# Aux_Outputs.net
KiCad netlist of a schematic drawn in Altium Designer
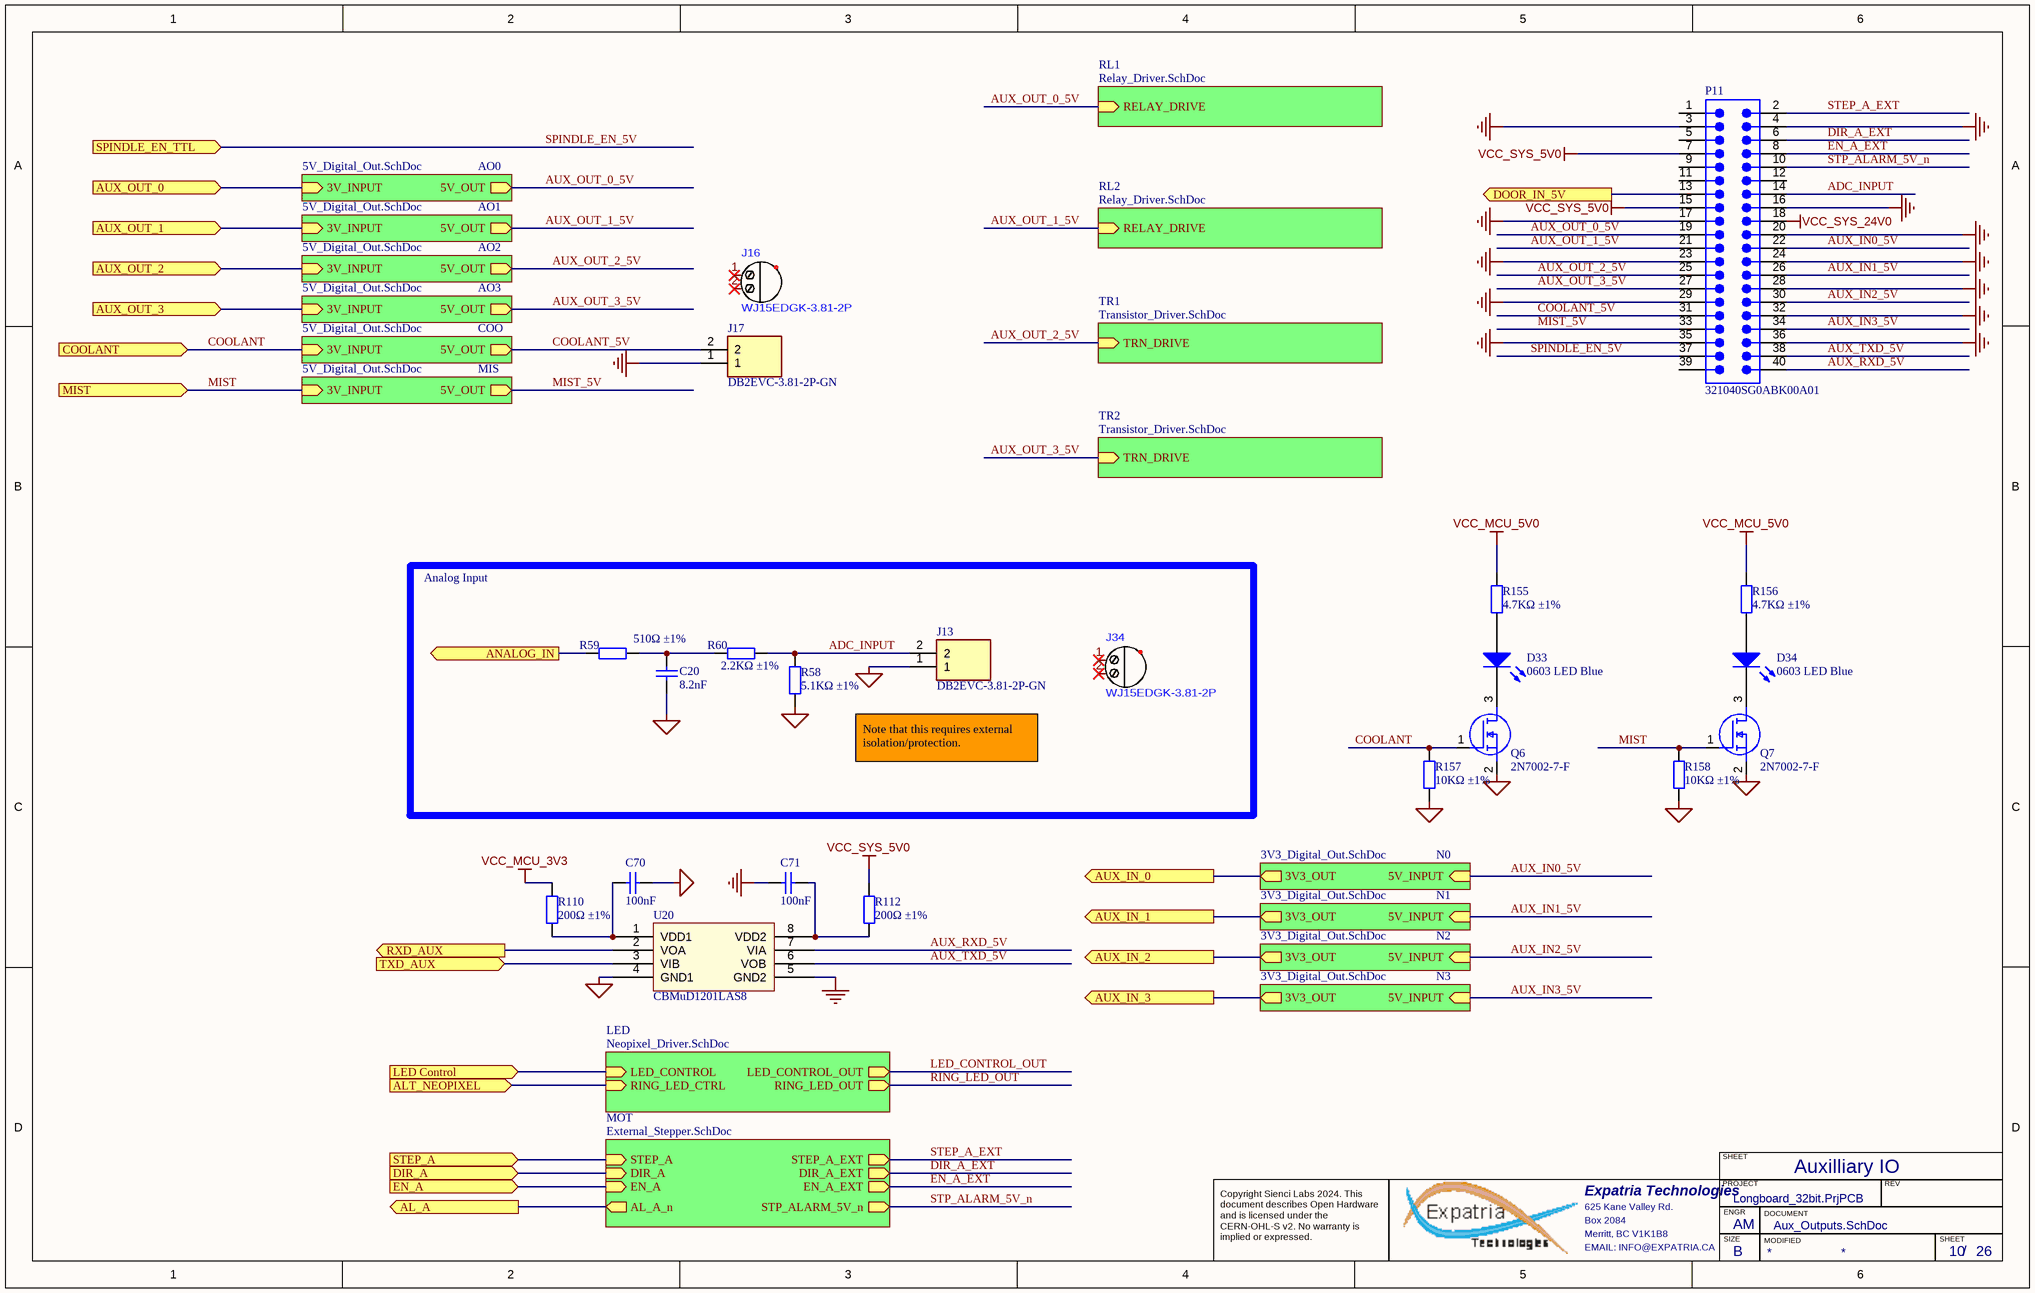
[diagram p0: Aux_Outputs.SchDoc]

(export (version "E")
  (design (tool "Eeschema 10.0.6"))
  (components
    (comp (ref "C20")
      (value "8.2nF")
      (footprint "0603_C")
      (description "50V 8.2nF X7R ±10% 0603 Multilayer Ceramic Capacitors MLCC - SMD/SMT ROHS")
      (fields (field (name "MANUFACTURER") "YAGEO") (field (name "TOLERANCE") "10%"))
      (libsource (lib "Sienci_Labs") (part "0603 8.2nF (822) 10% 50V"))
    )
    (comp (ref "C70")
      (value "100nF")
      (footprint "0402_C")
      (description "16V 100nF X7R ±10% 0402 Multilayer Ceramic Capacitors MLCC - SMD/SMT ROHS")
      (fields (field (name "MANUFACTURER") "Samsung Electro-Mechanics") (field (name "TOLERANCE") "10%"))
      (libsource (lib "Sienci_Labs") (part "0402 100nF (104) 10% 16V"))
    )
    (comp (ref "C71")
      (value "100nF")
      (footprint "0402_C")
      (description "16V 100nF X7R ±10% 0402 Multilayer Ceramic Capacitors MLCC - SMD/SMT ROHS")
      (fields (field (name "MANUFACTURER") "Samsung Electro-Mechanics") (field (name "TOLERANCE") "10%"))
      (libsource (lib "Sienci_Labs") (part "0402 100nF (104) 10% 16V"))
    )
    (comp (ref "D33")
      (value "0603 LED Blue")
      (footprint "0603_LED_S1 - BLUE")
      (description "Colorless transparence -40℃~+85℃ 465nm~475nm blue 120° 110mW 0603 Light Emitting Diodes (LED) ROHS")
      (fields
        (field (name "MANUFACTURER") "Everlight Elec")
        (field (name "MANUFACTURER PART NUMBER") "19-217/BHC-ZL1M2RY/3T")
      )
      (libsource (lib "Sienci_Labs") (part "0603 LED Blue"))
    )
    (comp (ref "D34")
      (value "0603 LED Blue")
      (footprint "0603_LED_S1 - BLUE")
      (description "Colorless transparence -40℃~+85℃ 465nm~475nm blue 120° 110mW 0603 Light Emitting Diodes (LED) ROHS")
      (fields
        (field (name "MANUFACTURER") "Everlight Elec")
        (field (name "MANUFACTURER PART NUMBER") "19-217/BHC-ZL1M2RY/3T")
      )
      (libsource (lib "Sienci_Labs") (part "0603 LED Blue"))
    )
    (comp (ref "J13")
      (value "DB2EVC-3.81-2P-GN")
      (footprint "CONN-TH_5P-P3.81_DB2EVC-3.81-2p")
      (description "3.81mm Green Board Edge/Receptacle-Close Push-Pull,P=3.81mm Pluggable System Terminal Block ROHS")
      (fields (field (name "MANUFACTURER") "DIBO"))
      (libsource (lib "Sienci_Labs") (part "DB2EVC-3.81-2P-GN"))
    )
    (comp (ref "J16")
      (value "WJ15EDGK-3.81-2P")
      (description "2 1 3.81mm Green Plug P=3.81mm Pluggable System Terminal Block ROHS")
      (fields (field (name "MANUFACTURER") "Ningbo"))
      (libsource (lib "Sienci_Labs") (part "WJ15EDGK-3.81-2P"))
    )
    (comp (ref "J17")
      (value "DB2EVC-3.81-2P-GN")
      (footprint "CONN-TH_5P-P3.81_DB2EVC-3.81-2p")
      (description "3.81mm Green Board Edge/Receptacle-Close Push-Pull,P=3.81mm Pluggable System Terminal Block ROHS")
      (fields (field (name "MANUFACTURER") "DIBO"))
      (libsource (lib "Sienci_Labs") (part "DB2EVC-3.81-2P-GN"))
    )
    (comp (ref "J34")
      (value "WJ15EDGK-3.81-2P")
      (description "2 1 3.81mm Green Plug P=3.81mm Pluggable System Terminal Block ROHS")
      (fields (field (name "MANUFACTURER") "Ningbo"))
      (libsource (lib "Sienci_Labs") (part "WJ15EDGK-3.81-2P"))
    )
    (comp (ref "P11")
      (value "321040SG0ABK00A01")
      (footprint "IDC-TH_40P-P2.54_321040SG0ABK00A01")
      (description "2.54mm Straight Gold Brass 20 Push - Pull 2.54mm 2 Straight,P=2.54mm IDC Connectors ROHS")
      (fields (field (name "MANUFACTURER") "JILN"))
      (libsource (lib "Sienci_Labs") (part "321040SG0ABK00A01"))
    )
    (comp (ref "Q6")
      (value "2N7002-7-F")
      (footprint "SOT-23(SOT-23-3)")
      (description "60V 115mA 7.5Ω@5V,50mA 370mW N Channel SOT-23 MOSFETs ROHS")
      (fields (field (name "MANUFACTURER") "Diodes Inc.") (field (name "MOUSER PART NUMBER") "621-2N7002-F"))
      (libsource (lib "Sienci_Labs") (part "2N7002-7-F"))
    )
    (comp (ref "Q7")
      (value "2N7002-7-F")
      (footprint "SOT-23(SOT-23-3)")
      (description "60V 115mA 7.5Ω@5V,50mA 370mW N Channel SOT-23 MOSFETs ROHS")
      (fields (field (name "MANUFACTURER") "Diodes Inc.") (field (name "MOUSER PART NUMBER") "621-2N7002-F"))
      (libsource (lib "Sienci_Labs") (part "2N7002-7-F"))
    )
    (comp (ref "R58")
      (value "5.1KΩ ±1%")
      (footprint "0402_R")
      (description "Chip resistor")
      (fields
        (field (name "MANUFACTURER") "Uniroyal Elec")
        (field (name "MANUFACTURER PART NUMBER") "0402WGF5101TCE")
      )
      (libsource (lib "RES") (part "0402 5.1K (5101) 1%"))
    )
    (comp (ref "R59")
      (value "510Ω ±1%")
      (footprint "0402_R")
      (description "Chip resistor")
      (fields
        (field (name "MANUFACTURER") "Uniroyal Elec")
        (field (name "MANUFACTURER PART NUMBER") "0402WGF5100TCE")
      )
      (libsource (lib "Sienci_Labs") (part "0402 510R (5100) 1%"))
    )
    (comp (ref "R60")
      (value "2.2KΩ ±1%")
      (footprint "0402_R")
      (description "Chip resistor")
      (fields
        (field (name "MANUFACTURER") "Uniroyal Elec")
        (field (name "MANUFACTURER PART NUMBER") "0402WGF2201TCE")
      )
      (libsource (lib "RES") (part "0402 2.2K (2201) 1%"))
    )
    (comp (ref "R110")
      (value "200Ω ±1%")
      (footprint "0402_R")
      (description "Chip resistor")
      (fields
        (field (name "MANUFACTURER") "Uniroyal Elec")
        (field (name "MANUFACTURER PART NUMBER") "0402WGF2000TCE")
      )
      (libsource (lib "RES") (part "0402 200R (2000) 1%"))
    )
    (comp (ref "R112")
      (value "200Ω ±1%")
      (footprint "0402_R")
      (description "Chip resistor")
      (fields
        (field (name "MANUFACTURER") "Uniroyal Elec")
        (field (name "MANUFACTURER PART NUMBER") "0402WGF2000TCE")
      )
      (libsource (lib "RES") (part "0402 200R (2000) 1%"))
    )
    (comp (ref "R155")
      (value "4.7KΩ ±1%")
      (footprint "0402_R")
      (description "Chip resistor")
      (fields
        (field (name "MANUFACTURER") "Uniroyal Elec")
        (field (name "MANUFACTURER PART NUMBER") "0402WGF4701TCE")
      )
      (libsource (lib "RES") (part "0402 4.7K (4701) 1%"))
    )
    (comp (ref "R156")
      (value "4.7KΩ ±1%")
      (footprint "0402_R")
      (description "Chip resistor")
      (fields
        (field (name "MANUFACTURER") "Uniroyal Elec")
        (field (name "MANUFACTURER PART NUMBER") "0402WGF4701TCE")
      )
      (libsource (lib "RES") (part "0402 4.7K (4701) 1%"))
    )
    (comp (ref "R157")
      (value "10KΩ ±1%")
      (footprint "0603_R")
      (description "Chip resistor")
      (fields
        (field (name "MANUFACTURER") "Uniroyal Elec")
        (field (name "MANUFACTURER PART NUMBER") "0603WAF1002T5E")
      )
      (libsource (lib "RES") (part "0603 10K (1002) 1%"))
    )
    (comp (ref "R158")
      (value "10KΩ ±1%")
      (footprint "0603_R")
      (description "Chip resistor")
      (fields
        (field (name "MANUFACTURER") "Uniroyal Elec")
        (field (name "MANUFACTURER PART NUMBER") "0603WAF1002T5E")
      )
      (libsource (lib "RES") (part "0603 10K (1002) 1%"))
    )
    (comp (ref "U20")
      (value "CBMuD1201LAS8")
      (footprint "SOIC-8_150mil")
      (description "Dual Channel Isolator")
      (fields (field (name "MANUFACTURER") "Corebai Microelectronics"))
      (libsource (lib "Sienci_Labs") (part "CBMuD1201LAS8"))
    )
  )
  (nets
    (net (code "1") (name "/ADC_INPUT") (class "Default")
      (node (ref "J13") (pin "2") (pinfunction "2_2") (pintype "passive"))
      (node (ref "P11") (pin "14") (pinfunction "14_14") (pintype "passive"))
      (node (ref "R58") (pin "2") (pinfunction "2_2") (pintype "passive"))
      (node (ref "R60") (pin "2") (pinfunction "2_2") (pintype "passive"))
    )
    (net (code "4") (name "/ANALOG_IN") (class "Default")
      (node (ref "R59") (pin "1") (pinfunction "1_1") (pintype "passive"))
    )
    (net (code "5") (name "/AUX_IN0_5V") (class "Default")
      (node (ref "P11") (pin "22") (pinfunction "22_22") (pintype "passive"))
    )
    (net (code "6") (name "/AUX_IN1_5V") (class "Default")
      (node (ref "P11") (pin "26") (pinfunction "26_26") (pintype "passive"))
    )
    (net (code "7") (name "/AUX_IN2_5V") (class "Default")
      (node (ref "P11") (pin "30") (pinfunction "30_30") (pintype "passive"))
    )
    (net (code "8") (name "/AUX_IN3_5V") (class "Default")
      (node (ref "P11") (pin "34") (pinfunction "34_34") (pintype "passive"))
    )
    (net (code "14") (name "/AUX_OUT_0_5V") (class "Default")
      (node (ref "P11") (pin "19") (pinfunction "19_19") (pintype "passive"))
    )
    (net (code "16") (name "/AUX_OUT_1_5V") (class "Default")
      (node (ref "P11") (pin "21") (pinfunction "21_21") (pintype "passive"))
    )
    (net (code "18") (name "/AUX_OUT_2_5V") (class "Default")
      (node (ref "P11") (pin "25") (pinfunction "25_25") (pintype "passive"))
    )
    (net (code "20") (name "/AUX_OUT_3_5V") (class "Default")
      (node (ref "P11") (pin "27") (pinfunction "27_27") (pintype "passive"))
    )
    (net (code "21") (name "/AUX_RXD_5V") (class "Default")
      (node (ref "P11") (pin "40") (pinfunction "40_40") (pintype "passive"))
      (node (ref "U20") (pin "7") (pinfunction "VIA_7") (pintype "passive"))
    )
    (net (code "22") (name "/AUX_TXD_5V") (class "Default")
      (node (ref "P11") (pin "38") (pinfunction "38_38") (pintype "passive"))
      (node (ref "U20") (pin "6") (pinfunction "VOB_6") (pintype "passive"))
    )
    (net (code "23") (name "/COOLANT") (class "Default")
      (node (ref "Q6") (pin "1") (pinfunction "G_1") (pintype "passive"))
      (node (ref "R157") (pin "2") (pinfunction "2_2") (pintype "passive"))
    )
    (net (code "24") (name "/COOLANT_5V") (class "Default")
      (node (ref "J17") (pin "2") (pinfunction "2_2") (pintype "passive"))
      (node (ref "P11") (pin "31") (pinfunction "31_31") (pintype "passive"))
    )
    (net (code "26") (name "/DIR_A_EXT") (class "Default")
      (node (ref "P11") (pin "6") (pinfunction "6_6") (pintype "passive"))
    )
    (net (code "27") (name "/DOOR_IN_5V") (class "Default")
      (node (ref "P11") (pin "13") (pinfunction "13_13") (pintype "passive"))
    )
    (net (code "29") (name "/EN_A_EXT") (class "Default")
      (node (ref "P11") (pin "8") (pinfunction "8_8") (pintype "passive"))
    )
    (net (code "32") (name "/MIST") (class "Default")
      (node (ref "Q7") (pin "1") (pinfunction "G_1") (pintype "passive"))
      (node (ref "R158") (pin "2") (pinfunction "2_2") (pintype "passive"))
    )
    (net (code "33") (name "/MIST_5V") (class "Default")
      (node (ref "P11") (pin "33") (pinfunction "33_33") (pintype "passive"))
    )
    (net (code "35") (name "/RXD_AUX") (class "Default")
      (node (ref "U20") (pin "2") (pinfunction "VOA_2") (pintype "passive"))
    )
    (net (code "36") (name "/SPINDLE_EN_5V") (class "Default")
      (node (ref "P11") (pin "37") (pinfunction "37_37") (pintype "passive"))
    )
    (net (code "38") (name "/STEP_A_EXT") (class "Default")
      (node (ref "P11") (pin "2") (pinfunction "2_2") (pintype "passive"))
    )
    (net (code "39") (name "/STP_ALARM_5V_n") (class "Default")
      (node (ref "P11") (pin "10") (pinfunction "10_10") (pintype "passive"))
    )
    (net (code "40") (name "/TXD_AUX") (class "Default")
      (node (ref "U20") (pin "3") (pinfunction "VIB_3") (pintype "passive"))
    )
    (net (code "41") (name "GND") (class "Default")
      (node (ref "C71") (pin "1") (pinfunction "1_1") (pintype "passive"))
      (node (ref "J17") (pin "1") (pinfunction "1_1") (pintype "passive"))
      (node (ref "P11") (pin "16") (pinfunction "16_16") (pintype "passive"))
      (node (ref "P11") (pin "17") (pinfunction "17_17") (pintype "passive"))
      (node (ref "P11") (pin "20") (pinfunction "20_20") (pintype "passive"))
      (node (ref "P11") (pin "23") (pinfunction "23_23") (pintype "passive"))
      (node (ref "P11") (pin "24") (pinfunction "24_24") (pintype "passive"))
      (node (ref "P11") (pin "28") (pinfunction "28_28") (pintype "passive"))
      (node (ref "P11") (pin "29") (pinfunction "29_29") (pintype "passive"))
      (node (ref "P11") (pin "3") (pinfunction "3_3") (pintype "passive"))
      (node (ref "P11") (pin "32") (pinfunction "32_32") (pintype "passive"))
      (node (ref "P11") (pin "35") (pinfunction "35_35") (pintype "passive"))
      (node (ref "P11") (pin "36") (pinfunction "36_36") (pintype "passive"))
      (node (ref "P11") (pin "4") (pinfunction "4_4") (pintype "passive"))
      (node (ref "U20") (pin "5") (pinfunction "GND2_5") (pintype "passive"))
    )
    (net (code "42") (name "MCU_GND") (class "Default")
      (node (ref "C20") (pin "1") (pinfunction "1_1") (pintype "passive"))
      (node (ref "C70") (pin "2") (pinfunction "2_2") (pintype "passive"))
      (node (ref "J13") (pin "1") (pinfunction "1_1") (pintype "passive"))
      (node (ref "Q6") (pin "2") (pinfunction "S_2") (pintype "passive"))
      (node (ref "Q7") (pin "2") (pinfunction "S_2") (pintype "passive"))
      (node (ref "R157") (pin "1") (pinfunction "1_1") (pintype "passive"))
      (node (ref "R158") (pin "1") (pinfunction "1_1") (pintype "passive"))
      (node (ref "R58") (pin "1") (pinfunction "1_1") (pintype "passive"))
      (node (ref "U20") (pin "4") (pinfunction "GND1_4") (pintype "passive"))
    )
    (net (code "43") (name "Net-(C20-Pad2)") (class "Default")
      (node (ref "C20") (pin "2") (pinfunction "2_2") (pintype "passive"))
      (node (ref "R59") (pin "2") (pinfunction "2_2") (pintype "passive"))
      (node (ref "R60") (pin "1") (pinfunction "1_1") (pintype "passive"))
    )
    (net (code "44") (name "Net-(D33-PadA)") (class "Default")
      (node (ref "D33") (pin "A") (pinfunction "A_A") (pintype "passive"))
      (node (ref "R155") (pin "1") (pinfunction "1_1") (pintype "passive"))
    )
    (net (code "45") (name "Net-(D34-PadA)") (class "Default")
      (node (ref "D34") (pin "A") (pinfunction "A_A") (pintype "passive"))
      (node (ref "R156") (pin "1") (pinfunction "1_1") (pintype "passive"))
    )
    (net (code "46") (name "Net-(Q6-D)") (class "Default")
      (node (ref "D33") (pin "K") (pinfunction "K_K") (pintype "passive"))
      (node (ref "Q6") (pin "3") (pinfunction "D_3") (pintype "passive"))
    )
    (net (code "47") (name "Net-(Q7-D)") (class "Default")
      (node (ref "D34") (pin "K") (pinfunction "K_K") (pintype "passive"))
      (node (ref "Q7") (pin "3") (pinfunction "D_3") (pintype "passive"))
    )
    (net (code "48") (name "Net-(U20-VDD1)") (class "Default")
      (node (ref "C70") (pin "1") (pinfunction "1_1") (pintype "passive"))
      (node (ref "R110") (pin "2") (pinfunction "2_2") (pintype "passive"))
      (node (ref "U20") (pin "1") (pinfunction "VDD1_1") (pintype "passive"))
    )
    (net (code "49") (name "Net-(U20-VDD2)") (class "Default")
      (node (ref "C71") (pin "2") (pinfunction "2_2") (pintype "passive"))
      (node (ref "R112") (pin "2") (pinfunction "2_2") (pintype "passive"))
      (node (ref "U20") (pin "8") (pinfunction "VDD2_8") (pintype "passive"))
    )
    (net (code "50") (name "VCC_MCU_3V3") (class "Default")
      (node (ref "R110") (pin "1") (pinfunction "1_1") (pintype "passive"))
    )
    (net (code "51") (name "VCC_MCU_5V0") (class "Default")
      (node (ref "R155") (pin "2") (pinfunction "2_2") (pintype "passive"))
      (node (ref "R156") (pin "2") (pinfunction "2_2") (pintype "passive"))
    )
    (net (code "52") (name "VCC_SYS_5V0") (class "Default")
      (node (ref "P11") (pin "15") (pinfunction "15_15") (pintype "passive"))
      (node (ref "P11") (pin "7") (pinfunction "7_7") (pintype "passive"))
      (node (ref "R112") (pin "1") (pinfunction "1_1") (pintype "passive"))
    )
    (net (code "53") (name "VCC_SYS_24V0") (class "Default")
      (node (ref "P11") (pin "18") (pinfunction "18_18") (pintype "passive"))
    )
    (net (code "54") (name "unconnected-(J16-Pad1)") (class "Default")
      (node (ref "J16") (pin "1") (pinfunction "1_1") (pintype "passive+no_connect"))
    )
    (net (code "55") (name "unconnected-(J16-Pad2)") (class "Default")
      (node (ref "J16") (pin "2") (pinfunction "2_2") (pintype "passive+no_connect"))
    )
    (net (code "56") (name "unconnected-(J34-Pad1)") (class "Default")
      (node (ref "J34") (pin "1") (pinfunction "1_1") (pintype "passive+no_connect"))
    )
    (net (code "57") (name "unconnected-(J34-Pad2)") (class "Default")
      (node (ref "J34") (pin "2") (pinfunction "2_2") (pintype "passive+no_connect"))
    )
    (net (code "58") (name "unconnected-(P11-Pad1)") (class "Default")
      (node (ref "P11") (pin "1") (pinfunction "1_1") (pintype "passive"))
    )
    (net (code "59") (name "unconnected-(P11-Pad5)") (class "Default")
      (node (ref "P11") (pin "5") (pinfunction "5_5") (pintype "passive"))
    )
    (net (code "60") (name "unconnected-(P11-Pad9)") (class "Default")
      (node (ref "P11") (pin "9") (pinfunction "9_9") (pintype "passive"))
    )
    (net (code "61") (name "unconnected-(P11-Pad11)") (class "Default")
      (node (ref "P11") (pin "11") (pinfunction "11_11") (pintype "passive"))
    )
    (net (code "62") (name "unconnected-(P11-Pad12)") (class "Default")
      (node (ref "P11") (pin "12") (pinfunction "12_12") (pintype "passive"))
    )
    (net (code "63") (name "unconnected-(P11-Pad39)") (class "Default")
      (node (ref "P11") (pin "39") (pinfunction "39_39") (pintype "passive"))
    )
  )
)
